# shift_serial.net
KiCad netlist of a schematic drawn in EAGLE
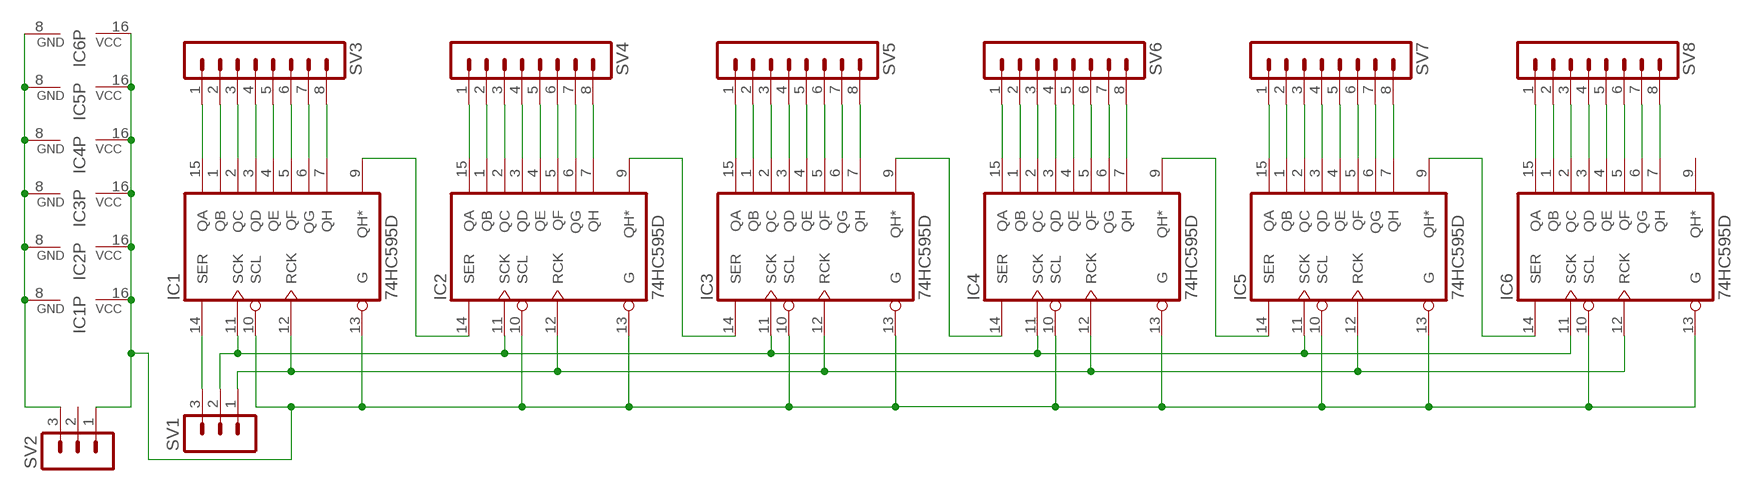
[diagram p0: schematic, sheet 1]

(export (version "E")
  (design (tool "Eeschema 10.0.6"))
  (components
    (comp (ref "IC1")
      (value "74HC595D")
      (footprint "eagle-import:SO16")
      (libsource (lib "eagle-import") (part "74595DHC"))
    )
    (comp (ref "IC2")
      (value "74HC595D")
      (footprint "eagle-import:SO16")
      (libsource (lib "eagle-import") (part "74595DHC"))
    )
    (comp (ref "IC3")
      (value "74HC595D")
      (footprint "eagle-import:SO16")
      (libsource (lib "eagle-import") (part "74595DHC"))
    )
    (comp (ref "IC4")
      (value "74HC595D")
      (footprint "eagle-import:SO16")
      (libsource (lib "eagle-import") (part "74595DHC"))
    )
    (comp (ref "IC5")
      (value "74HC595D")
      (footprint "eagle-import:SO16")
      (libsource (lib "eagle-import") (part "74595DHC"))
    )
    (comp (ref "IC6")
      (value "74HC595D")
      (footprint "eagle-import:SO16")
      (libsource (lib "eagle-import") (part "74595DHC"))
    )
    (comp (ref "SV1")
      (value "MA03-1")
      (footprint "eagle-import:MA03-1")
      (libsource (lib "eagle-import") (part "MA03-1"))
    )
    (comp (ref "SV2")
      (value "MA03-1")
      (footprint "eagle-import:MA03-1")
      (libsource (lib "eagle-import") (part "MA03-1"))
    )
    (comp (ref "SV3")
      (value "MA08-1")
      (footprint "eagle-import:MA08-1")
      (libsource (lib "eagle-import") (part "MA08-1"))
    )
    (comp (ref "SV4")
      (value "MA08-1")
      (footprint "eagle-import:MA08-1")
      (libsource (lib "eagle-import") (part "MA08-1"))
    )
    (comp (ref "SV5")
      (value "MA08-1")
      (footprint "eagle-import:MA08-1")
      (libsource (lib "eagle-import") (part "MA08-1"))
    )
    (comp (ref "SV6")
      (value "MA08-1")
      (footprint "eagle-import:MA08-1")
      (libsource (lib "eagle-import") (part "MA08-1"))
    )
    (comp (ref "SV7")
      (value "MA08-1")
      (footprint "eagle-import:MA08-1")
      (libsource (lib "eagle-import") (part "MA08-1"))
    )
    (comp (ref "SV8")
      (value "MA08-1")
      (footprint "eagle-import:MA08-1")
      (libsource (lib "eagle-import") (part "MA08-1"))
    )
  )
  (nets
    (net (code "1") (name "Net-(IC1A-G)") (class "Default")
      (node (ref "IC1") (pin "10") (pinfunction "SCL_10") (pintype "input"))
      (node (ref "IC1") (pin "13") (pinfunction "G_13") (pintype "input"))
      (node (ref "IC1") (pin "16") (pinfunction "VCC_16") (pintype "power_in"))
      (node (ref "IC2") (pin "10") (pinfunction "SCL_10") (pintype "input"))
      (node (ref "IC2") (pin "13") (pinfunction "G_13") (pintype "input"))
      (node (ref "IC2") (pin "16") (pinfunction "VCC_16") (pintype "power_in"))
      (node (ref "IC3") (pin "10") (pinfunction "SCL_10") (pintype "input"))
      (node (ref "IC3") (pin "13") (pinfunction "G_13") (pintype "input"))
      (node (ref "IC3") (pin "16") (pinfunction "VCC_16") (pintype "power_in"))
      (node (ref "IC4") (pin "10") (pinfunction "SCL_10") (pintype "input"))
      (node (ref "IC4") (pin "13") (pinfunction "G_13") (pintype "input"))
      (node (ref "IC4") (pin "16") (pinfunction "VCC_16") (pintype "power_in"))
      (node (ref "IC5") (pin "10") (pinfunction "SCL_10") (pintype "input"))
      (node (ref "IC5") (pin "13") (pinfunction "G_13") (pintype "input"))
      (node (ref "IC5") (pin "16") (pinfunction "VCC_16") (pintype "power_in"))
      (node (ref "IC6") (pin "10") (pinfunction "SCL_10") (pintype "input"))
      (node (ref "IC6") (pin "13") (pinfunction "G_13") (pintype "input"))
      (node (ref "IC6") (pin "16") (pinfunction "VCC_16") (pintype "power_in"))
      (node (ref "SV2") (pin "1") (pinfunction "1_1") (pintype "passive"))
    )
    (net (code "2") (name "Net-(IC1A-QA)") (class "Default")
      (node (ref "IC1") (pin "15") (pinfunction "QA_15") (pintype "tri_state"))
      (node (ref "SV3") (pin "1") (pinfunction "1_1") (pintype "passive"))
    )
    (net (code "3") (name "Net-(IC1A-QB)") (class "Default")
      (node (ref "IC1") (pin "1") (pinfunction "QB_1") (pintype "tri_state"))
      (node (ref "SV3") (pin "2") (pinfunction "2_2") (pintype "passive"))
    )
    (net (code "4") (name "Net-(IC1A-QC)") (class "Default")
      (node (ref "IC1") (pin "2") (pinfunction "QC_2") (pintype "tri_state"))
      (node (ref "SV3") (pin "3") (pinfunction "3_3") (pintype "passive"))
    )
    (net (code "5") (name "Net-(IC1A-QD)") (class "Default")
      (node (ref "IC1") (pin "3") (pinfunction "QD_3") (pintype "tri_state"))
      (node (ref "SV3") (pin "4") (pinfunction "4_4") (pintype "passive"))
    )
    (net (code "6") (name "Net-(IC1A-QE)") (class "Default")
      (node (ref "IC1") (pin "4") (pinfunction "QE_4") (pintype "tri_state"))
      (node (ref "SV3") (pin "5") (pinfunction "5_5") (pintype "passive"))
    )
    (net (code "7") (name "Net-(IC1A-QF)") (class "Default")
      (node (ref "IC1") (pin "5") (pinfunction "QF_5") (pintype "tri_state"))
      (node (ref "SV3") (pin "6") (pinfunction "6_6") (pintype "passive"))
    )
    (net (code "8") (name "Net-(IC1A-QG)") (class "Default")
      (node (ref "IC1") (pin "6") (pinfunction "QG_6") (pintype "tri_state"))
      (node (ref "SV3") (pin "7") (pinfunction "7_7") (pintype "passive"))
    )
    (net (code "9") (name "Net-(IC1A-QH)") (class "Default")
      (node (ref "IC1") (pin "7") (pinfunction "QH_7") (pintype "tri_state"))
      (node (ref "SV3") (pin "8") (pinfunction "8_8") (pintype "passive"))
    )
    (net (code "10") (name "Net-(IC1A-QH*)") (class "Default")
      (node (ref "IC1") (pin "9") (pinfunction "QH*_9") (pintype "tri_state"))
      (node (ref "IC2") (pin "14") (pinfunction "SER_14") (pintype "input"))
    )
    (net (code "11") (name "Net-(IC1A-RCK)") (class "Default")
      (node (ref "IC1") (pin "12") (pinfunction "RCK_12") (pintype "input"))
      (node (ref "IC2") (pin "12") (pinfunction "RCK_12") (pintype "input"))
      (node (ref "IC3") (pin "12") (pinfunction "RCK_12") (pintype "input"))
      (node (ref "IC4") (pin "12") (pinfunction "RCK_12") (pintype "input"))
      (node (ref "IC5") (pin "12") (pinfunction "RCK_12") (pintype "input"))
      (node (ref "IC6") (pin "12") (pinfunction "RCK_12") (pintype "input"))
      (node (ref "SV1") (pin "1") (pinfunction "1_1") (pintype "passive"))
    )
    (net (code "12") (name "Net-(IC1A-SCK)") (class "Default")
      (node (ref "IC1") (pin "11") (pinfunction "SCK_11") (pintype "input"))
      (node (ref "IC2") (pin "11") (pinfunction "SCK_11") (pintype "input"))
      (node (ref "IC3") (pin "11") (pinfunction "SCK_11") (pintype "input"))
      (node (ref "IC4") (pin "11") (pinfunction "SCK_11") (pintype "input"))
      (node (ref "IC5") (pin "11") (pinfunction "SCK_11") (pintype "input"))
      (node (ref "IC6") (pin "11") (pinfunction "SCK_11") (pintype "input"))
      (node (ref "SV1") (pin "2") (pinfunction "2_2") (pintype "passive"))
    )
    (net (code "13") (name "Net-(IC1A-SER)") (class "Default")
      (node (ref "IC1") (pin "14") (pinfunction "SER_14") (pintype "input"))
      (node (ref "SV1") (pin "3") (pinfunction "3_3") (pintype "passive"))
    )
    (net (code "14") (name "Net-(IC1B-GND)") (class "Default")
      (node (ref "IC1") (pin "8") (pinfunction "GND_8") (pintype "power_in"))
      (node (ref "IC2") (pin "8") (pinfunction "GND_8") (pintype "power_in"))
      (node (ref "IC3") (pin "8") (pinfunction "GND_8") (pintype "power_in"))
      (node (ref "IC4") (pin "8") (pinfunction "GND_8") (pintype "power_in"))
      (node (ref "IC5") (pin "8") (pinfunction "GND_8") (pintype "power_in"))
      (node (ref "IC6") (pin "8") (pinfunction "GND_8") (pintype "power_in"))
      (node (ref "SV2") (pin "3") (pinfunction "3_3") (pintype "passive"))
    )
    (net (code "15") (name "Net-(IC2A-QA)") (class "Default")
      (node (ref "IC2") (pin "15") (pinfunction "QA_15") (pintype "tri_state"))
      (node (ref "SV4") (pin "1") (pinfunction "1_1") (pintype "passive"))
    )
    (net (code "16") (name "Net-(IC2A-QB)") (class "Default")
      (node (ref "IC2") (pin "1") (pinfunction "QB_1") (pintype "tri_state"))
      (node (ref "SV4") (pin "2") (pinfunction "2_2") (pintype "passive"))
    )
    (net (code "17") (name "Net-(IC2A-QC)") (class "Default")
      (node (ref "IC2") (pin "2") (pinfunction "QC_2") (pintype "tri_state"))
      (node (ref "SV4") (pin "3") (pinfunction "3_3") (pintype "passive"))
    )
    (net (code "18") (name "Net-(IC2A-QD)") (class "Default")
      (node (ref "IC2") (pin "3") (pinfunction "QD_3") (pintype "tri_state"))
      (node (ref "SV4") (pin "4") (pinfunction "4_4") (pintype "passive"))
    )
    (net (code "19") (name "Net-(IC2A-QE)") (class "Default")
      (node (ref "IC2") (pin "4") (pinfunction "QE_4") (pintype "tri_state"))
      (node (ref "SV4") (pin "5") (pinfunction "5_5") (pintype "passive"))
    )
    (net (code "20") (name "Net-(IC2A-QF)") (class "Default")
      (node (ref "IC2") (pin "5") (pinfunction "QF_5") (pintype "tri_state"))
      (node (ref "SV4") (pin "6") (pinfunction "6_6") (pintype "passive"))
    )
    (net (code "21") (name "Net-(IC2A-QG)") (class "Default")
      (node (ref "IC2") (pin "6") (pinfunction "QG_6") (pintype "tri_state"))
      (node (ref "SV4") (pin "7") (pinfunction "7_7") (pintype "passive"))
    )
    (net (code "22") (name "Net-(IC2A-QH)") (class "Default")
      (node (ref "IC2") (pin "7") (pinfunction "QH_7") (pintype "tri_state"))
      (node (ref "SV4") (pin "8") (pinfunction "8_8") (pintype "passive"))
    )
    (net (code "23") (name "Net-(IC2A-QH*)") (class "Default")
      (node (ref "IC2") (pin "9") (pinfunction "QH*_9") (pintype "tri_state"))
      (node (ref "IC3") (pin "14") (pinfunction "SER_14") (pintype "input"))
    )
    (net (code "24") (name "Net-(IC3A-QA)") (class "Default")
      (node (ref "IC3") (pin "15") (pinfunction "QA_15") (pintype "tri_state"))
      (node (ref "SV5") (pin "1") (pinfunction "1_1") (pintype "passive"))
    )
    (net (code "25") (name "Net-(IC3A-QB)") (class "Default")
      (node (ref "IC3") (pin "1") (pinfunction "QB_1") (pintype "tri_state"))
      (node (ref "SV5") (pin "2") (pinfunction "2_2") (pintype "passive"))
    )
    (net (code "26") (name "Net-(IC3A-QC)") (class "Default")
      (node (ref "IC3") (pin "2") (pinfunction "QC_2") (pintype "tri_state"))
      (node (ref "SV5") (pin "3") (pinfunction "3_3") (pintype "passive"))
    )
    (net (code "27") (name "Net-(IC3A-QD)") (class "Default")
      (node (ref "IC3") (pin "3") (pinfunction "QD_3") (pintype "tri_state"))
      (node (ref "SV5") (pin "4") (pinfunction "4_4") (pintype "passive"))
    )
    (net (code "28") (name "Net-(IC3A-QE)") (class "Default")
      (node (ref "IC3") (pin "4") (pinfunction "QE_4") (pintype "tri_state"))
      (node (ref "SV5") (pin "5") (pinfunction "5_5") (pintype "passive"))
    )
    (net (code "29") (name "Net-(IC3A-QF)") (class "Default")
      (node (ref "IC3") (pin "5") (pinfunction "QF_5") (pintype "tri_state"))
      (node (ref "SV5") (pin "6") (pinfunction "6_6") (pintype "passive"))
    )
    (net (code "30") (name "Net-(IC3A-QG)") (class "Default")
      (node (ref "IC3") (pin "6") (pinfunction "QG_6") (pintype "tri_state"))
      (node (ref "SV5") (pin "7") (pinfunction "7_7") (pintype "passive"))
    )
    (net (code "31") (name "Net-(IC3A-QH)") (class "Default")
      (node (ref "IC3") (pin "7") (pinfunction "QH_7") (pintype "tri_state"))
      (node (ref "SV5") (pin "8") (pinfunction "8_8") (pintype "passive"))
    )
    (net (code "32") (name "Net-(IC3A-QH*)") (class "Default")
      (node (ref "IC3") (pin "9") (pinfunction "QH*_9") (pintype "tri_state"))
      (node (ref "IC4") (pin "14") (pinfunction "SER_14") (pintype "input"))
    )
    (net (code "33") (name "Net-(IC4A-QA)") (class "Default")
      (node (ref "IC4") (pin "15") (pinfunction "QA_15") (pintype "tri_state"))
      (node (ref "SV6") (pin "1") (pinfunction "1_1") (pintype "passive"))
    )
    (net (code "34") (name "Net-(IC4A-QB)") (class "Default")
      (node (ref "IC4") (pin "1") (pinfunction "QB_1") (pintype "tri_state"))
      (node (ref "SV6") (pin "2") (pinfunction "2_2") (pintype "passive"))
    )
    (net (code "35") (name "Net-(IC4A-QC)") (class "Default")
      (node (ref "IC4") (pin "2") (pinfunction "QC_2") (pintype "tri_state"))
      (node (ref "SV6") (pin "3") (pinfunction "3_3") (pintype "passive"))
    )
    (net (code "36") (name "Net-(IC4A-QD)") (class "Default")
      (node (ref "IC4") (pin "3") (pinfunction "QD_3") (pintype "tri_state"))
      (node (ref "SV6") (pin "4") (pinfunction "4_4") (pintype "passive"))
    )
    (net (code "37") (name "Net-(IC4A-QE)") (class "Default")
      (node (ref "IC4") (pin "4") (pinfunction "QE_4") (pintype "tri_state"))
      (node (ref "SV6") (pin "5") (pinfunction "5_5") (pintype "passive"))
    )
    (net (code "38") (name "Net-(IC4A-QF)") (class "Default")
      (node (ref "IC4") (pin "5") (pinfunction "QF_5") (pintype "tri_state"))
      (node (ref "SV6") (pin "6") (pinfunction "6_6") (pintype "passive"))
    )
    (net (code "39") (name "Net-(IC4A-QG)") (class "Default")
      (node (ref "IC4") (pin "6") (pinfunction "QG_6") (pintype "tri_state"))
      (node (ref "SV6") (pin "7") (pinfunction "7_7") (pintype "passive"))
    )
    (net (code "40") (name "Net-(IC4A-QH)") (class "Default")
      (node (ref "IC4") (pin "7") (pinfunction "QH_7") (pintype "tri_state"))
      (node (ref "SV6") (pin "8") (pinfunction "8_8") (pintype "passive"))
    )
    (net (code "41") (name "Net-(IC4A-QH*)") (class "Default")
      (node (ref "IC4") (pin "9") (pinfunction "QH*_9") (pintype "tri_state"))
      (node (ref "IC5") (pin "14") (pinfunction "SER_14") (pintype "input"))
    )
    (net (code "42") (name "Net-(IC5A-QA)") (class "Default")
      (node (ref "IC5") (pin "15") (pinfunction "QA_15") (pintype "tri_state"))
      (node (ref "SV7") (pin "1") (pinfunction "1_1") (pintype "passive"))
    )
    (net (code "43") (name "Net-(IC5A-QB)") (class "Default")
      (node (ref "IC5") (pin "1") (pinfunction "QB_1") (pintype "tri_state"))
      (node (ref "SV7") (pin "2") (pinfunction "2_2") (pintype "passive"))
    )
    (net (code "44") (name "Net-(IC5A-QC)") (class "Default")
      (node (ref "IC5") (pin "2") (pinfunction "QC_2") (pintype "tri_state"))
      (node (ref "SV7") (pin "3") (pinfunction "3_3") (pintype "passive"))
    )
    (net (code "45") (name "Net-(IC5A-QD)") (class "Default")
      (node (ref "IC5") (pin "3") (pinfunction "QD_3") (pintype "tri_state"))
      (node (ref "SV7") (pin "4") (pinfunction "4_4") (pintype "passive"))
    )
    (net (code "46") (name "Net-(IC5A-QE)") (class "Default")
      (node (ref "IC5") (pin "4") (pinfunction "QE_4") (pintype "tri_state"))
      (node (ref "SV7") (pin "5") (pinfunction "5_5") (pintype "passive"))
    )
    (net (code "47") (name "Net-(IC5A-QF)") (class "Default")
      (node (ref "IC5") (pin "5") (pinfunction "QF_5") (pintype "tri_state"))
      (node (ref "SV7") (pin "6") (pinfunction "6_6") (pintype "passive"))
    )
    (net (code "48") (name "Net-(IC5A-QG)") (class "Default")
      (node (ref "IC5") (pin "6") (pinfunction "QG_6") (pintype "tri_state"))
      (node (ref "SV7") (pin "7") (pinfunction "7_7") (pintype "passive"))
    )
    (net (code "49") (name "Net-(IC5A-QH)") (class "Default")
      (node (ref "IC5") (pin "7") (pinfunction "QH_7") (pintype "tri_state"))
      (node (ref "SV7") (pin "8") (pinfunction "8_8") (pintype "passive"))
    )
    (net (code "50") (name "Net-(IC5A-QH*)") (class "Default")
      (node (ref "IC5") (pin "9") (pinfunction "QH*_9") (pintype "tri_state"))
      (node (ref "IC6") (pin "14") (pinfunction "SER_14") (pintype "input"))
    )
    (net (code "51") (name "Net-(IC6A-QA)") (class "Default")
      (node (ref "IC6") (pin "15") (pinfunction "QA_15") (pintype "tri_state"))
      (node (ref "SV8") (pin "1") (pinfunction "1_1") (pintype "passive"))
    )
    (net (code "52") (name "Net-(IC6A-QB)") (class "Default")
      (node (ref "IC6") (pin "1") (pinfunction "QB_1") (pintype "tri_state"))
      (node (ref "SV8") (pin "2") (pinfunction "2_2") (pintype "passive"))
    )
    (net (code "53") (name "Net-(IC6A-QC)") (class "Default")
      (node (ref "IC6") (pin "2") (pinfunction "QC_2") (pintype "tri_state"))
      (node (ref "SV8") (pin "3") (pinfunction "3_3") (pintype "passive"))
    )
    (net (code "54") (name "Net-(IC6A-QD)") (class "Default")
      (node (ref "IC6") (pin "3") (pinfunction "QD_3") (pintype "tri_state"))
      (node (ref "SV8") (pin "4") (pinfunction "4_4") (pintype "passive"))
    )
    (net (code "55") (name "Net-(IC6A-QE)") (class "Default")
      (node (ref "IC6") (pin "4") (pinfunction "QE_4") (pintype "tri_state"))
      (node (ref "SV8") (pin "5") (pinfunction "5_5") (pintype "passive"))
    )
    (net (code "56") (name "Net-(IC6A-QF)") (class "Default")
      (node (ref "IC6") (pin "5") (pinfunction "QF_5") (pintype "tri_state"))
      (node (ref "SV8") (pin "6") (pinfunction "6_6") (pintype "passive"))
    )
    (net (code "57") (name "Net-(IC6A-QG)") (class "Default")
      (node (ref "IC6") (pin "6") (pinfunction "QG_6") (pintype "tri_state"))
      (node (ref "SV8") (pin "7") (pinfunction "7_7") (pintype "passive"))
    )
    (net (code "58") (name "Net-(IC6A-QH)") (class "Default")
      (node (ref "IC6") (pin "7") (pinfunction "QH_7") (pintype "tri_state"))
      (node (ref "SV8") (pin "8") (pinfunction "8_8") (pintype "passive"))
    )
    (net (code "59") (name "unconnected-(IC6A-QH*-Pad9)") (class "Default")
      (node (ref "IC6") (pin "9") (pinfunction "QH*_9") (pintype "tri_state"))
    )
    (net (code "60") (name "unconnected-(SV2-Pad2)") (class "Default")
      (node (ref "SV2") (pin "2") (pinfunction "2_2") (pintype "passive"))
    )
  )
)
